# CAN.net
KiCad netlist of a schematic drawn in EAGLE
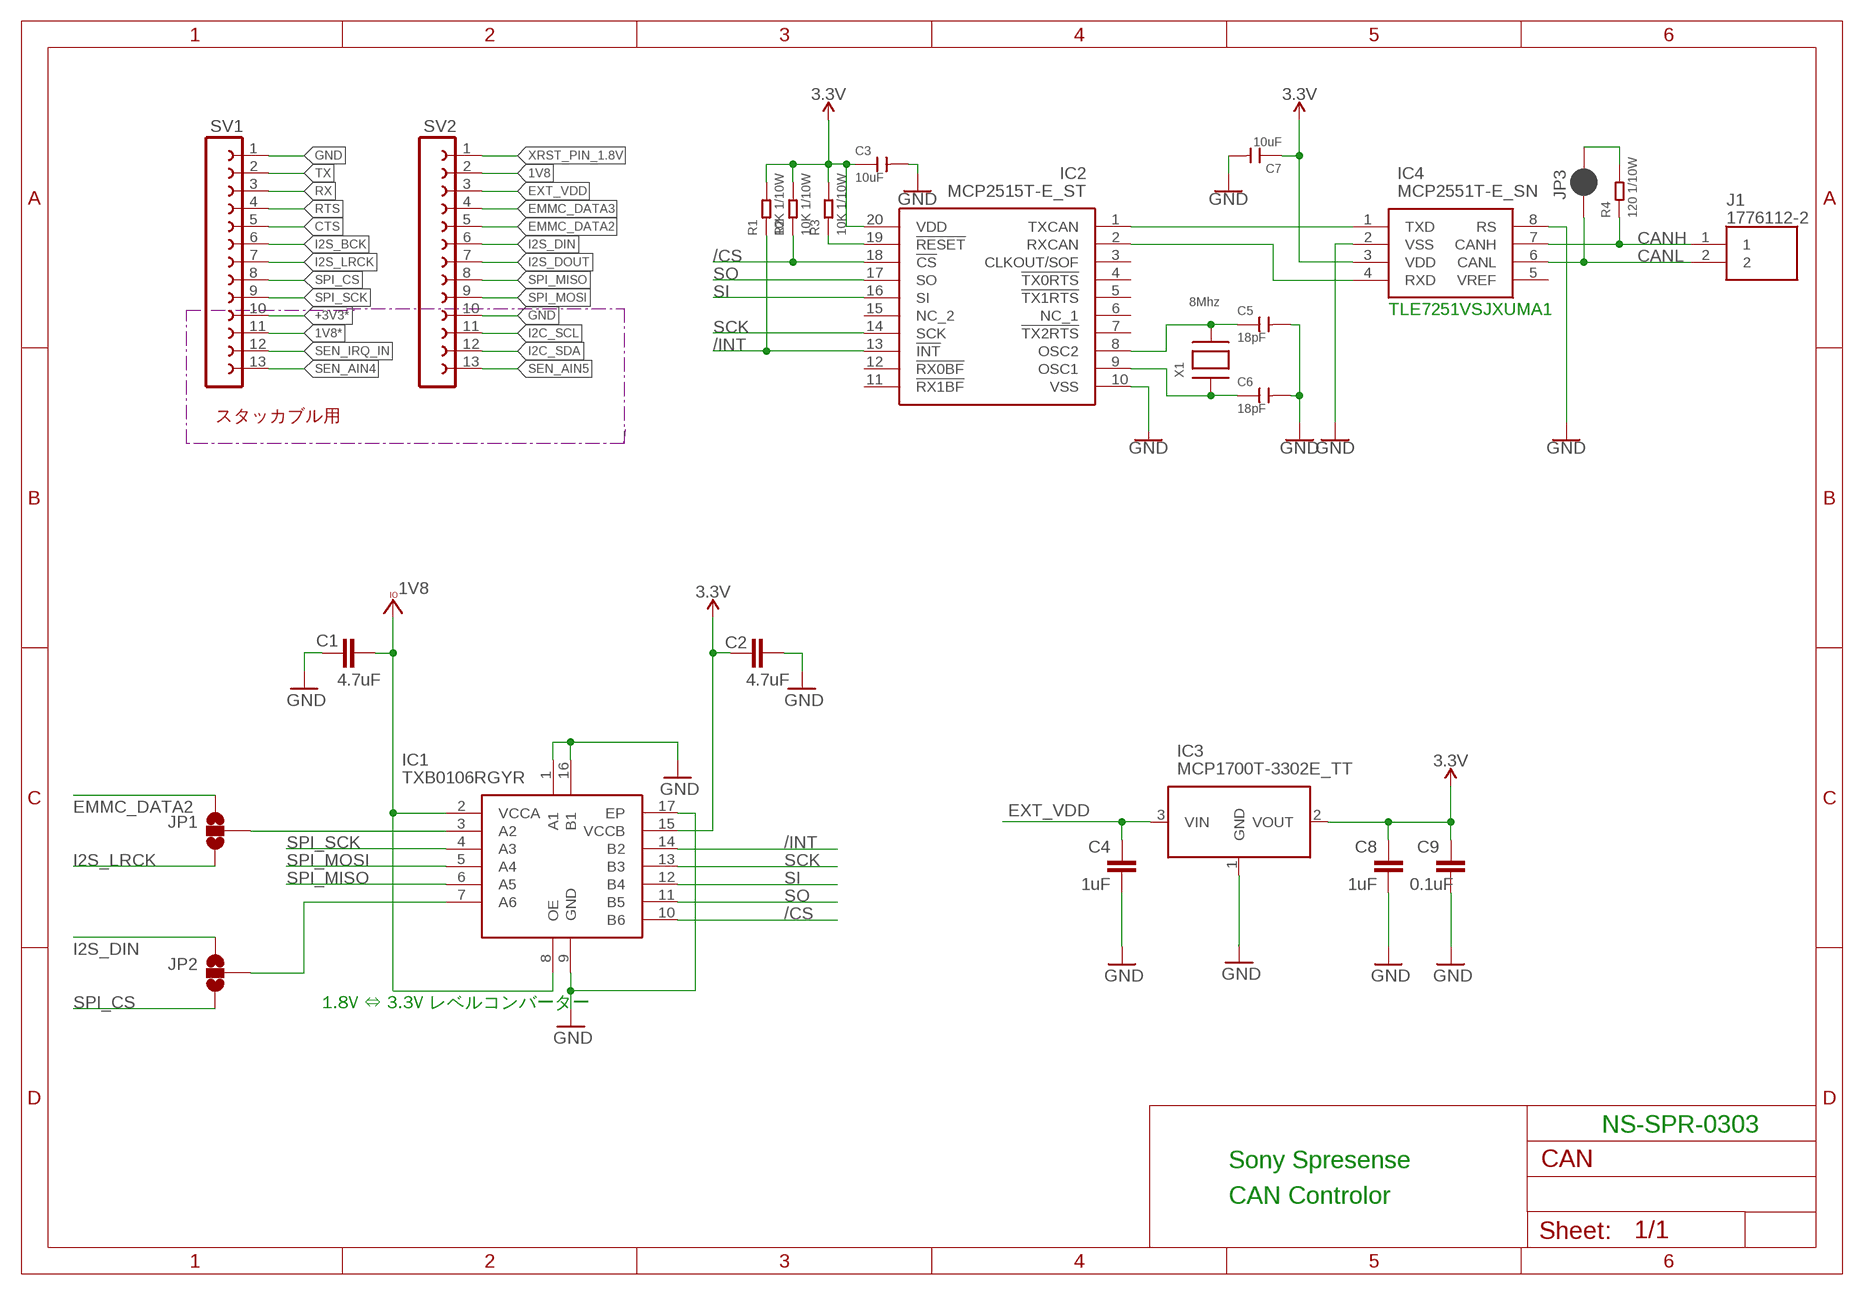
[diagram p0: schematic, sheet 1]

(export (version "E")
  (design (tool "Eeschema 10.0.6"))
  (components
    (comp (ref "C1")
      (value "4.7uF")
      (footprint "eagle-import:C0603K")
      (libsource (lib "eagle-import") (part "C-EUC0603K"))
    )
    (comp (ref "C2")
      (value "4.7uF")
      (footprint "eagle-import:C0603K")
      (libsource (lib "eagle-import") (part "C-EUC0603K"))
    )
    (comp (ref "C3")
      (value "10uF")
      (footprint "eagle-import:C0603")
      (fields (field (name "MPN") "CC0603JRNPO9BN270"))
      (libsource (lib "eagle-import") (part "CERAMIC-27PF-50V-5%-NPO(0603)"))
    )
    (comp (ref "C4")
      (value "1uF")
      (footprint "eagle-import:C0603K")
      (libsource (lib "eagle-import") (part "C-EUC0603K"))
    )
    (comp (ref "C5")
      (value "18pF")
      (footprint "eagle-import:C0603")
      (fields (field (name "MPN") "CC0603JRNPO9BN270"))
      (libsource (lib "eagle-import") (part "CERAMIC-27PF-50V-5%-NPO(0603)"))
    )
    (comp (ref "C6")
      (value "18pF")
      (footprint "eagle-import:C0603")
      (fields (field (name "MPN") "CC0603JRNPO9BN270"))
      (libsource (lib "eagle-import") (part "CERAMIC-27PF-50V-5%-NPO(0603)"))
    )
    (comp (ref "C7")
      (value "10uF")
      (footprint "eagle-import:C0603")
      (fields (field (name "MPN") "CC0603JRNPO9BN270"))
      (libsource (lib "eagle-import") (part "CERAMIC-27PF-50V-5%-NPO(0603)"))
    )
    (comp (ref "C8")
      (value "1uF")
      (footprint "eagle-import:C0603K")
      (libsource (lib "eagle-import") (part "C-EUC0603K"))
    )
    (comp (ref "C9")
      (value "0.1uF")
      (footprint "eagle-import:C0603K")
      (libsource (lib "eagle-import") (part "C-EUC0603K"))
    )
    (comp (ref "IC1")
      (value "TXB0106RGYR")
      (footprint "eagle-import:SN74CBT3257CRGYR")
      (fields (field (name "MOUSER_PART_NUMBER") "595-TXB0106RGYR"))
      (libsource (lib "eagle-import") (part "TXB0106RGYR"))
    )
    (comp (ref "IC2")
      (value "MCP2515T-E_ST")
      (footprint "eagle-import:SOP65P640X120-20N")
      (fields
        (field (name "MANUFACTURER_PART_NUMBER") "MCP2515T-E/ST")
        (field (name "MOUSER_PART_NUMBER") "579-MCP2515T-E/ST")
      )
      (libsource (lib "eagle-import") (part "MCP2515T-E_ST"))
    )
    (comp (ref "IC3")
      (value "MCP1700T-3302E_TT")
      (footprint "eagle-import:SOT95P237X112-3N")
      (fields
        (field (name "MANUFACTURER_PART_NUMBER") "MCP1700T-3302E/TT")
        (field (name "MOUSER_PART_NUMBER") "579-MCP1700T3302E/TT")
      )
      (libsource (lib "eagle-import") (part "MCP1700T-3302E_TT"))
    )
    (comp (ref "IC4")
      (value "MCP2551T-E_SN")
      (footprint "eagle-import:SOIC127P600X175-8N")
      (fields
        (field (name "MANUFACTURER_PART_NUMBER") "MCP2551T-E/SN")
        (field (name "MOUSER_PART_NUMBER") "579-MCP2551T-E/SN")
      )
      (libsource (lib "eagle-import") (part "MCP2551T-E_SN"))
    )
    (comp (ref "J1")
      (value "1776112-2")
      (footprint "eagle-import:SHDR2W90P0X348_1X2_700X730X850")
      (fields (field (name "MOUSER_PART_NUMBER") "571-1776112-2"))
      (libsource (lib "eagle-import") (part "1776112-2"))
    )
    (comp (ref "JP1")
      (value "JUMPER-SMT_3_NO_NO-SILK")
      (footprint "eagle-import:SMT-JUMPER_3_NO_NO-SILK")
      (libsource (lib "eagle-import") (part "JUMPER-SMT_3_NO_NO-SILK"))
    )
    (comp (ref "JP2")
      (value "JUMPER-SMT_3_NO_NO-SILK")
      (footprint "eagle-import:SMT-JUMPER_3_NO_NO-SILK")
      (libsource (lib "eagle-import") (part "JUMPER-SMT_3_NO_NO-SILK"))
    )
    (comp (ref "JP3")
      (value "JUMPER-SMT_2_NC_PASTE_NO-SILK")
      (footprint "eagle-import:SMT-JUMPER_2_NC_PASTE_NO-SILK")
      (libsource (lib "eagle-import") (part "JUMPER-SMT_2_NC_PASTE_NO-SILK"))
    )
    (comp (ref "R1")
      (value "10K 1/10W")
      (footprint "eagle-import:R0603")
      (fields (field (name "MPN") "RC0603JR-0710KL"))
      (libsource (lib "eagle-import") (part "SMD-RES-10K-5%-1/10W(0603)"))
    )
    (comp (ref "R2")
      (value "10K 1/10W")
      (footprint "eagle-import:R0603")
      (fields (field (name "MPN") "RC0603JR-0710KL"))
      (libsource (lib "eagle-import") (part "SMD-RES-10K-5%-1/10W(0603)"))
    )
    (comp (ref "R3")
      (value "10K 1/10W")
      (footprint "eagle-import:R0603")
      (fields (field (name "MPN") "RC0603JR-0710KL"))
      (libsource (lib "eagle-import") (part "SMD-RES-10K-5%-1/10W(0603)"))
    )
    (comp (ref "R4")
      (value "120 1/10W")
      (footprint "eagle-import:R0603")
      (fields (field (name "MPN") "RC0603JR-0710KL"))
      (libsource (lib "eagle-import") (part "SMD-RES-10K-5%-1/10W(0603)"))
    )
    (comp (ref "SV1")
      (value "FE13-1")
      (footprint "eagle-import:FE13")
      (libsource (lib "eagle-import") (part "FE13-1"))
    )
    (comp (ref "SV2")
      (value "FE13-1")
      (footprint "eagle-import:FE13")
      (libsource (lib "eagle-import") (part "FE13-1"))
    )
    (comp (ref "X1")
      (value "8Mhz")
      (footprint "eagle-import:HC49UP")
      (libsource (lib "eagle-import") (part "306010040_XTAL_12MHZ_HC49UP"))
    )
  )
  (nets
    (net (code "1") (name "+3V3*") (class "Default")
      (node (ref "SV1") (pin "10") (pinfunction "10_10") (pintype "passive"))
    )
    (net (code "2") (name "/CANH") (class "Default")
      (node (ref "IC4") (pin "7") (pinfunction "CANH_7") (pintype "bidirectional"))
      (node (ref "J1") (pin "1") (pinfunction "1_1") (pintype "bidirectional"))
      (node (ref "R4") (pin "1") (pinfunction "1_1") (pintype "passive"))
    )
    (net (code "3") (name "/CANL") (class "Default")
      (node (ref "IC4") (pin "6") (pinfunction "CANL_6") (pintype "bidirectional"))
      (node (ref "J1") (pin "2") (pinfunction "2_2") (pintype "bidirectional"))
      (node (ref "JP3") (pin "1") (pinfunction "1_1") (pintype "passive"))
    )
    (net (code "4") (name "/SCK") (class "Default")
      (node (ref "IC1") (pin "13") (pinfunction "B3_13") (pintype "bidirectional"))
      (node (ref "IC2") (pin "14") (pinfunction "SCK_14") (pintype "bidirectional"))
    )
    (net (code "5") (name "/SI") (class "Default")
      (node (ref "IC1") (pin "12") (pinfunction "B4_12") (pintype "bidirectional"))
      (node (ref "IC2") (pin "16") (pinfunction "SI_16") (pintype "bidirectional"))
    )
    (net (code "6") (name "/SO") (class "Default")
      (node (ref "IC1") (pin "11") (pinfunction "B5_11") (pintype "bidirectional"))
      (node (ref "IC2") (pin "17") (pinfunction "SO_17") (pintype "bidirectional"))
    )
    (net (code "7") (name "/{slash}CS") (class "Default")
      (node (ref "IC1") (pin "10") (pinfunction "B6_10") (pintype "bidirectional"))
      (node (ref "IC2") (pin "18") (pinfunction "~{CS}_18") (pintype "bidirectional"))
      (node (ref "R2") (pin "1") (pinfunction "1_1") (pintype "passive"))
    )
    (net (code "8") (name "/{slash}INT") (class "Default")
      (node (ref "IC1") (pin "14") (pinfunction "B2_14") (pintype "bidirectional"))
      (node (ref "IC2") (pin "13") (pinfunction "~{INT}_13") (pintype "bidirectional"))
      (node (ref "R1") (pin "1") (pinfunction "1_1") (pintype "passive"))
    )
    (net (code "9") (name "1V8") (class "Default")
      (node (ref "C1") (pin "2") (pinfunction "2_2") (pintype "passive"))
      (node (ref "IC1") (pin "2") (pinfunction "VCCA_2") (pintype "bidirectional"))
      (node (ref "IC1") (pin "8") (pinfunction "OE_8") (pintype "bidirectional"))
      (node (ref "SV2") (pin "2") (pinfunction "2_2") (pintype "passive"))
    )
    (net (code "10") (name "1V8*") (class "Default")
      (node (ref "SV1") (pin "11") (pinfunction "11_11") (pintype "passive"))
    )
    (net (code "11") (name "3.3V") (class "Default")
      (node (ref "C2") (pin "1") (pinfunction "1_1") (pintype "passive"))
      (node (ref "C3") (pin "1") (pinfunction "1_1") (pintype "passive"))
      (node (ref "C7") (pin "1") (pinfunction "1_1") (pintype "passive"))
      (node (ref "C8") (pin "1") (pinfunction "1_1") (pintype "passive"))
      (node (ref "C9") (pin "1") (pinfunction "1_1") (pintype "passive"))
      (node (ref "IC1") (pin "15") (pinfunction "VCCB_15") (pintype "bidirectional"))
      (node (ref "IC2") (pin "20") (pinfunction "VDD_20") (pintype "bidirectional"))
      (node (ref "IC3") (pin "2") (pinfunction "VOUT_2") (pintype "output"))
      (node (ref "IC4") (pin "3") (pinfunction "VDD_3") (pintype "bidirectional"))
      (node (ref "R1") (pin "2") (pinfunction "2_2") (pintype "passive"))
      (node (ref "R2") (pin "2") (pinfunction "2_2") (pintype "passive"))
      (node (ref "R3") (pin "2") (pinfunction "2_2") (pintype "passive"))
    )
    (net (code "12") (name "CTS") (class "Default")
      (node (ref "SV1") (pin "5") (pinfunction "5_5") (pintype "passive"))
    )
    (net (code "13") (name "EMMC_DATA2") (class "Default")
      (node (ref "JP1") (pin "1") (pinfunction "1_1") (pintype "passive"))
      (node (ref "SV2") (pin "5") (pinfunction "5_5") (pintype "passive"))
    )
    (net (code "14") (name "EMMC_DATA3") (class "Default")
      (node (ref "SV2") (pin "4") (pinfunction "4_4") (pintype "passive"))
    )
    (net (code "15") (name "EXT_VDD") (class "Default")
      (node (ref "C4") (pin "1") (pinfunction "1_1") (pintype "passive"))
      (node (ref "IC3") (pin "3") (pinfunction "VIN_3") (pintype "input"))
      (node (ref "SV2") (pin "3") (pinfunction "3_3") (pintype "passive"))
    )
    (net (code "16") (name "GND") (class "Default")
      (node (ref "C1") (pin "1") (pinfunction "1_1") (pintype "passive"))
      (node (ref "C2") (pin "2") (pinfunction "2_2") (pintype "passive"))
      (node (ref "C3") (pin "2") (pinfunction "2_2") (pintype "passive"))
      (node (ref "C4") (pin "2") (pinfunction "2_2") (pintype "passive"))
      (node (ref "C5") (pin "2") (pinfunction "2_2") (pintype "passive"))
      (node (ref "C6") (pin "2") (pinfunction "2_2") (pintype "passive"))
      (node (ref "C7") (pin "2") (pinfunction "2_2") (pintype "passive"))
      (node (ref "C8") (pin "2") (pinfunction "2_2") (pintype "passive"))
      (node (ref "C9") (pin "2") (pinfunction "2_2") (pintype "passive"))
      (node (ref "IC1") (pin "1") (pinfunction "A1_1") (pintype "bidirectional"))
      (node (ref "IC1") (pin "16") (pinfunction "B1_16") (pintype "bidirectional"))
      (node (ref "IC1") (pin "17") (pinfunction "EP_17") (pintype "bidirectional"))
      (node (ref "IC1") (pin "9") (pinfunction "GND_9") (pintype "bidirectional"))
      (node (ref "IC2") (pin "10") (pinfunction "VSS_10") (pintype "bidirectional"))
      (node (ref "IC3") (pin "1") (pinfunction "GND_1") (pintype "power_in"))
      (node (ref "IC4") (pin "2") (pinfunction "VSS_2") (pintype "bidirectional"))
      (node (ref "IC4") (pin "8") (pinfunction "RS_8") (pintype "bidirectional"))
      (node (ref "SV1") (pin "1") (pinfunction "1_1") (pintype "passive"))
      (node (ref "SV2") (pin "10") (pinfunction "10_10") (pintype "passive"))
    )
    (net (code "17") (name "I2C_SCL") (class "Default")
      (node (ref "SV2") (pin "11") (pinfunction "11_11") (pintype "passive"))
    )
    (net (code "18") (name "I2C_SDA") (class "Default")
      (node (ref "SV2") (pin "12") (pinfunction "12_12") (pintype "passive"))
    )
    (net (code "19") (name "I2S_BCK") (class "Default")
      (node (ref "SV1") (pin "6") (pinfunction "6_6") (pintype "passive"))
    )
    (net (code "20") (name "I2S_DIN") (class "Default")
      (node (ref "JP2") (pin "1") (pinfunction "1_1") (pintype "passive"))
      (node (ref "SV2") (pin "6") (pinfunction "6_6") (pintype "passive"))
    )
    (net (code "21") (name "I2S_DOUT") (class "Default")
      (node (ref "SV2") (pin "7") (pinfunction "7_7") (pintype "passive"))
    )
    (net (code "22") (name "I2S_LRCK") (class "Default")
      (node (ref "JP1") (pin "3") (pinfunction "3_3") (pintype "passive"))
      (node (ref "SV1") (pin "7") (pinfunction "7_7") (pintype "passive"))
    )
    (net (code "23") (name "Net-(IC1-A2)") (class "Default")
      (node (ref "IC1") (pin "3") (pinfunction "A2_3") (pintype "bidirectional"))
      (node (ref "JP1") (pin "2") (pinfunction "2_2") (pintype "passive"))
    )
    (net (code "24") (name "Net-(IC1-A6)") (class "Default")
      (node (ref "IC1") (pin "7") (pinfunction "A6_7") (pintype "bidirectional"))
      (node (ref "JP2") (pin "2") (pinfunction "2_2") (pintype "passive"))
    )
    (net (code "25") (name "Net-(IC2-OSC1)") (class "Default")
      (node (ref "C6") (pin "1") (pinfunction "1_1") (pintype "passive"))
      (node (ref "IC2") (pin "9") (pinfunction "OSC1_9") (pintype "bidirectional"))
      (node (ref "X1") (pin "P$1") (pinfunction "P$1_P$1") (pintype "passive"))
    )
    (net (code "26") (name "Net-(IC2-OSC2)") (class "Default")
      (node (ref "C5") (pin "1") (pinfunction "1_1") (pintype "passive"))
      (node (ref "IC2") (pin "8") (pinfunction "OSC2_8") (pintype "bidirectional"))
      (node (ref "X1") (pin "P$2") (pinfunction "P$2_P$2") (pintype "passive"))
    )
    (net (code "27") (name "Net-(IC2-RXCAN)") (class "Default")
      (node (ref "IC2") (pin "2") (pinfunction "RXCAN_2") (pintype "bidirectional"))
      (node (ref "IC4") (pin "4") (pinfunction "RXD_4") (pintype "bidirectional"))
    )
    (net (code "28") (name "Net-(IC2-TXCAN)") (class "Default")
      (node (ref "IC2") (pin "1") (pinfunction "TXCAN_1") (pintype "bidirectional"))
      (node (ref "IC4") (pin "1") (pinfunction "TXD_1") (pintype "bidirectional"))
    )
    (net (code "29") (name "Net-(IC2-~{RESET})") (class "Default")
      (node (ref "IC2") (pin "19") (pinfunction "~{RESET}_19") (pintype "bidirectional"))
      (node (ref "R3") (pin "1") (pinfunction "1_1") (pintype "passive"))
    )
    (net (code "30") (name "Net-(JP3-Pad2)") (class "Default")
      (node (ref "JP3") (pin "2") (pinfunction "2_2") (pintype "passive"))
      (node (ref "R4") (pin "2") (pinfunction "2_2") (pintype "passive"))
    )
    (net (code "31") (name "RTS") (class "Default")
      (node (ref "SV1") (pin "4") (pinfunction "4_4") (pintype "passive"))
    )
    (net (code "32") (name "RX") (class "Default")
      (node (ref "SV1") (pin "3") (pinfunction "3_3") (pintype "passive"))
    )
    (net (code "33") (name "SEN_AIN4") (class "Default")
      (node (ref "SV1") (pin "13") (pinfunction "13_13") (pintype "passive"))
    )
    (net (code "34") (name "SEN_AIN5") (class "Default")
      (node (ref "SV2") (pin "13") (pinfunction "13_13") (pintype "passive"))
    )
    (net (code "35") (name "SEN_IRQ_IN") (class "Default")
      (node (ref "SV1") (pin "12") (pinfunction "12_12") (pintype "passive"))
    )
    (net (code "36") (name "SPI_CS") (class "Default")
      (node (ref "JP2") (pin "3") (pinfunction "3_3") (pintype "passive"))
      (node (ref "SV1") (pin "8") (pinfunction "8_8") (pintype "passive"))
    )
    (net (code "37") (name "SPI_MISO") (class "Default")
      (node (ref "IC1") (pin "6") (pinfunction "A5_6") (pintype "bidirectional"))
      (node (ref "SV2") (pin "8") (pinfunction "8_8") (pintype "passive"))
    )
    (net (code "38") (name "SPI_MOSI") (class "Default")
      (node (ref "IC1") (pin "5") (pinfunction "A4_5") (pintype "bidirectional"))
      (node (ref "SV2") (pin "9") (pinfunction "9_9") (pintype "passive"))
    )
    (net (code "39") (name "SPI_SCK") (class "Default")
      (node (ref "IC1") (pin "4") (pinfunction "A3_4") (pintype "bidirectional"))
      (node (ref "SV1") (pin "9") (pinfunction "9_9") (pintype "passive"))
    )
    (net (code "40") (name "TX") (class "Default")
      (node (ref "SV1") (pin "2") (pinfunction "2_2") (pintype "passive"))
    )
    (net (code "41") (name "XRST_PIN_1.8V") (class "Default")
      (node (ref "SV2") (pin "1") (pinfunction "1_1") (pintype "passive"))
    )
    (net (code "42") (name "unconnected-(IC2-CLKOUT{slash}SOF-Pad3)") (class "Default")
      (node (ref "IC2") (pin "3") (pinfunction "CLKOUT/SOF_3") (pintype "bidirectional"))
    )
    (net (code "43") (name "unconnected-(IC2-NC_1-Pad6)") (class "Default")
      (node (ref "IC2") (pin "6") (pinfunction "NC_1_6") (pintype "bidirectional"))
    )
    (net (code "44") (name "unconnected-(IC2-NC_2-Pad15)") (class "Default")
      (node (ref "IC2") (pin "15") (pinfunction "NC_2_15") (pintype "bidirectional"))
    )
    (net (code "45") (name "unconnected-(IC2-~{RX0BF}-Pad12)") (class "Default")
      (node (ref "IC2") (pin "12") (pinfunction "~{RX0BF}_12") (pintype "bidirectional"))
    )
    (net (code "46") (name "unconnected-(IC2-~{RX1BF}-Pad11)") (class "Default")
      (node (ref "IC2") (pin "11") (pinfunction "~{RX1BF}_11") (pintype "bidirectional"))
    )
    (net (code "47") (name "unconnected-(IC2-~{TX0RTS}-Pad4)") (class "Default")
      (node (ref "IC2") (pin "4") (pinfunction "~{TX0RTS}_4") (pintype "bidirectional"))
    )
    (net (code "48") (name "unconnected-(IC2-~{TX1RTS}-Pad5)") (class "Default")
      (node (ref "IC2") (pin "5") (pinfunction "~{TX1RTS}_5") (pintype "bidirectional"))
    )
    (net (code "49") (name "unconnected-(IC2-~{TX2RTS}-Pad7)") (class "Default")
      (node (ref "IC2") (pin "7") (pinfunction "~{TX2RTS}_7") (pintype "bidirectional"))
    )
    (net (code "50") (name "unconnected-(IC4-VREF-Pad5)") (class "Default")
      (node (ref "IC4") (pin "5") (pinfunction "VREF_5") (pintype "bidirectional"))
    )
  )
)
